# Keyfinder_Alert.net
KiCad netlist of a schematic drawn in Altium Designer
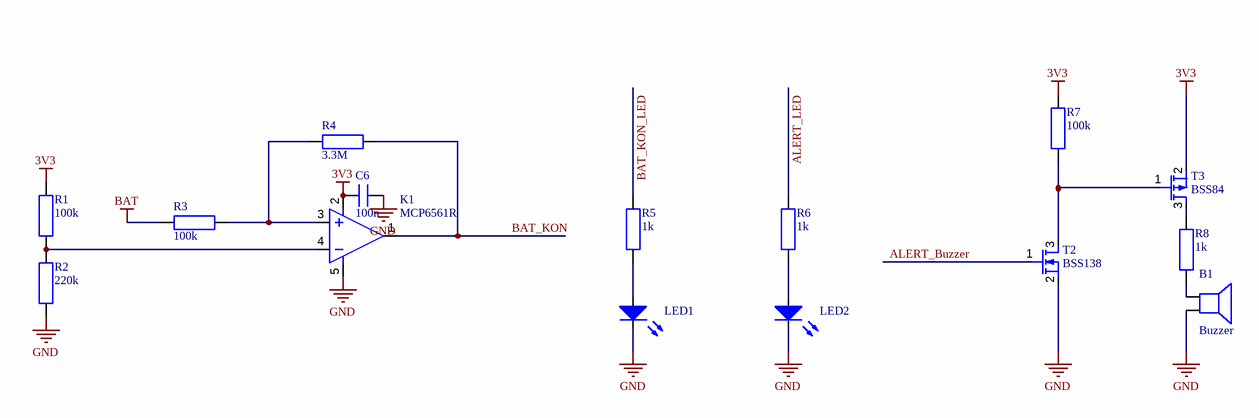
[diagram p0: Keyfinder_Alert.SchDoc]

(export (version "E")
  (design (tool "Eeschema 10.0.6"))
  (components
    (comp (ref "B1")
      (value "Buzzer")
      (footprint "piezo_ele")
      (libsource (lib "DEVICE_HSLU") (part "SPEAKER"))
    )
    (comp (ref "C6")
      (value "100n")
      (footprint "0805_C")
      (description "Normaler Kondensator")
      (libsource (lib "MainBoard") (part "C?"))
    )
    (comp (ref "K1") (value "MCP6561R") (footprint "SOT23-5") (libsource (lib "MainBoard") (part "OPAMP")))
    (comp (ref "LED1") (value "~") (footprint "0805_LED") (libsource (lib "Sch_Lib") (part "LED")))
    (comp (ref "LED2") (value "~") (footprint "0805_LED") (libsource (lib "Sch_Lib") (part "LED")))
    (comp (ref "R1")
      (value "100k")
      (footprint "0805_R")
      (description "Normaler Widerstand")
      (libsource (lib "MainBoard") (part "R?"))
    )
    (comp (ref "R2")
      (value "220k")
      (footprint "0805_R")
      (description "Normaler Widerstand")
      (libsource (lib "MainBoard") (part "R?"))
    )
    (comp (ref "R3")
      (value "100k")
      (footprint "0805_R")
      (description "Normaler Widerstand")
      (libsource (lib "MainBoard") (part "R?"))
    )
    (comp (ref "R4")
      (value "3.3M")
      (footprint "0805_R")
      (description "Normaler Widerstand")
      (libsource (lib "MainBoard") (part "R?"))
    )
    (comp (ref "R5")
      (value "1k")
      (footprint "0805_R")
      (description "Normaler Widerstand")
      (libsource (lib "MainBoard") (part "R?"))
    )
    (comp (ref "R6")
      (value "1k")
      (footprint "0805_R")
      (description "Normaler Widerstand")
      (libsource (lib "MainBoard") (part "R?"))
    )
    (comp (ref "R7")
      (value "100k")
      (footprint "0805_R")
      (description "Normaler Widerstand")
      (libsource (lib "MainBoard") (part "R?"))
    )
    (comp (ref "R8")
      (value "1k")
      (footprint "0805_R")
      (description "Normaler Widerstand")
      (libsource (lib "MainBoard") (part "R?"))
    )
    (comp (ref "T2")
      (value "BSS138")
      (footprint "SOT23-3")
      (description "MOSFET-N 1D,2G,3S")
      (libsource (lib "Sch_Lib") (part "MOSFET-N 1D,2G,3S"))
    )
    (comp (ref "T3")
      (value "BSS84")
      (footprint "SOT23-3")
      (description "MOSFET-P 1D,2G,3S")
      (libsource (lib "Sch_Lib") (part "MOSFET-P 1D,2G,3S"))
    )
  )
  (nets
    (net (code "1") (name "/ALERT_Buzzer") (class "Default")
      (node (ref "T2") (pin "1") (pinfunction "G_1") (pintype "passive"))
    )
    (net (code "2") (name "/ALERT_LED") (class "Default") (node (ref "R6") (pin "1") (pintype "passive")))
    (net (code "3") (name "/BAT_KON") (class "Default")
      (node (ref "K1") (pin "1") (pinfunction "1_1") (pintype "passive"))
      (node (ref "R4") (pin "1") (pintype "passive"))
    )
    (net (code "4") (name "/BAT_KON_LED") (class "Default") (node (ref "R5") (pin "1") (pintype "passive")))
    (net (code "5") (name "3V3") (class "Default")
      (node (ref "C6") (pin "2") (pinfunction "2_2") (pintype "passive"))
      (node (ref "K1") (pin "2") (pinfunction "2_2") (pintype "passive"))
      (node (ref "R1") (pin "1") (pintype "passive"))
      (node (ref "R7") (pin "1") (pintype "passive"))
      (node (ref "T3") (pin "2") (pinfunction "S_2") (pintype "passive"))
    )
    (net (code "6") (name "BAT") (class "Default") (node (ref "R3") (pin "2") (pintype "passive")))
    (net (code "7") (name "GND") (class "Default")
      (node (ref "B1") (pin "2") (pintype "passive"))
      (node (ref "C6") (pin "1") (pinfunction "1_1") (pintype "passive"))
      (node (ref "K1") (pin "5") (pinfunction "5_5") (pintype "passive"))
      (node (ref "LED1") (pin "2") (pinfunction "K_2") (pintype "passive"))
      (node (ref "LED2") (pin "2") (pinfunction "K_2") (pintype "passive"))
      (node (ref "R2") (pin "2") (pintype "passive"))
      (node (ref "T2") (pin "2") (pinfunction "S_2") (pintype "passive"))
    )
    (net (code "8") (name "Net-(B1-Pad1)") (class "Default")
      (node (ref "B1") (pin "1") (pintype "passive"))
      (node (ref "R8") (pin "2") (pintype "passive"))
    )
    (net (code "9") (name "Net-(K1-Pad3)") (class "Default")
      (node (ref "K1") (pin "3") (pinfunction "3_3") (pintype "passive"))
      (node (ref "R3") (pin "1") (pintype "passive"))
      (node (ref "R4") (pin "2") (pintype "passive"))
    )
    (net (code "10") (name "Net-(K1-Pad4)") (class "Default")
      (node (ref "K1") (pin "4") (pinfunction "4_4") (pintype "passive"))
      (node (ref "R1") (pin "2") (pintype "passive"))
      (node (ref "R2") (pin "1") (pintype "passive"))
    )
    (net (code "11") (name "Net-(LED1-A)") (class "Default")
      (node (ref "LED1") (pin "1") (pinfunction "A_1") (pintype "passive"))
      (node (ref "R5") (pin "2") (pintype "passive"))
    )
    (net (code "12") (name "Net-(LED2-A)") (class "Default")
      (node (ref "LED2") (pin "1") (pinfunction "A_1") (pintype "passive"))
      (node (ref "R6") (pin "2") (pintype "passive"))
    )
    (net (code "13") (name "Net-(T2-D)") (class "Default")
      (node (ref "R7") (pin "2") (pintype "passive"))
      (node (ref "T2") (pin "3") (pinfunction "D_3") (pintype "passive"))
      (node (ref "T3") (pin "1") (pinfunction "G_1") (pintype "passive"))
    )
    (net (code "14") (name "Net-(T3-D)") (class "Default")
      (node (ref "R8") (pin "1") (pintype "passive"))
      (node (ref "T3") (pin "3") (pinfunction "D_3") (pintype "passive"))
    )
  )
)
